# RP2040_Microcontroller.net
KiCad netlist of a schematic drawn in Altium Designer
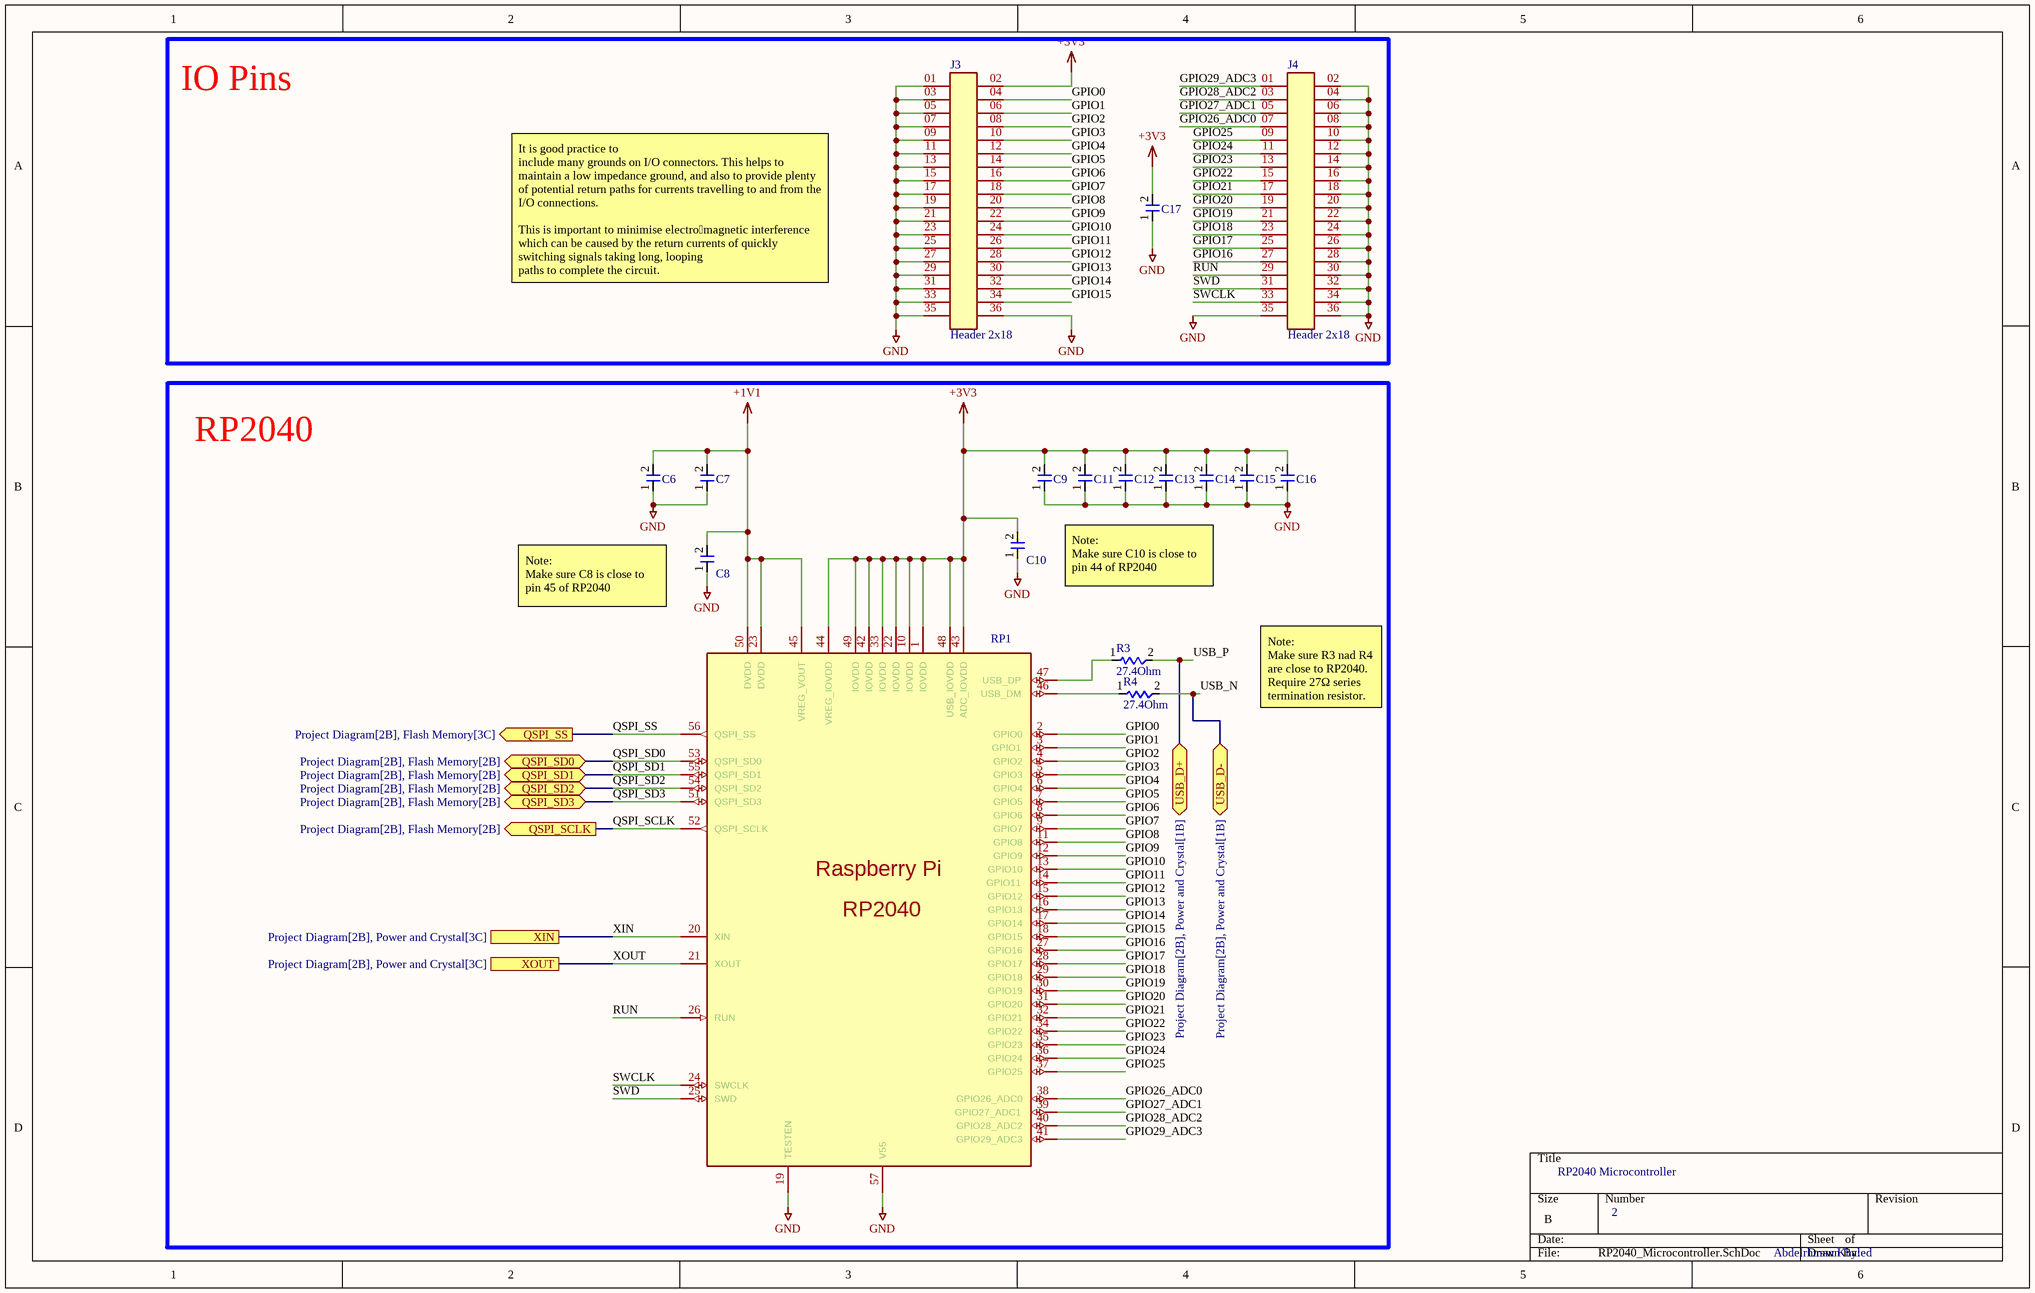
[diagram p0: RP2040_Microcontroller.SchDoc]

(export (version "E")
  (design (tool "Eeschema 10.0.6"))
  (components
    (comp (ref "C6")
      (value "100 nF")
      (footprint "CC0603KRX5R8BB104")
      (description "100 nF ±10% 25V Ceramic Capacitor X5R 0603 (1608 Metric)")
      (fields (field (name "PART NUMBER") "CL21A106KOQNNNE"))
      (libsource (lib "RP2040_Integrated_Library") (part "CC0603KRX5R8BB104"))
    )
    (comp (ref "C7")
      (value "100 nF")
      (footprint "CC0603KRX5R8BB104")
      (description "100 nF ±10% 25V Ceramic Capacitor X5R 0603 (1608 Metric)")
      (fields (field (name "PART NUMBER") "CL21A106KOQNNNE"))
      (libsource (lib "RP2040_Integrated_Library") (part "CC0603KRX5R8BB104"))
    )
    (comp (ref "C8")
      (value "1UF Cap")
      (footprint "C0805C105K4RAC7800")
      (description "1 µF ±10% 16V Ceramic Capacitor X7R 0805 (2012 Metric)")
      (fields (field (name "PART NUMBER") "C0805C105K4RAC7800"))
      (libsource (lib "RP2040_Integrated_Library") (part "C0805C105K4RAC7800"))
    )
    (comp (ref "C9")
      (value "100 nF")
      (footprint "CC0603KRX5R8BB104")
      (description "100 nF ±10% 25V Ceramic Capacitor X5R 0603 (1608 Metric)")
      (fields (field (name "PART NUMBER") "CL21A106KOQNNNE"))
      (libsource (lib "RP2040_Integrated_Library") (part "CC0603KRX5R8BB104"))
    )
    (comp (ref "C10")
      (value "1UF Cap")
      (footprint "C0805C105K4RAC7800")
      (description "1 µF ±10% 16V Ceramic Capacitor X7R 0805 (2012 Metric)")
      (fields (field (name "PART NUMBER") "C0805C105K4RAC7800"))
      (libsource (lib "RP2040_Integrated_Library") (part "C0805C105K4RAC7800"))
    )
    (comp (ref "C11")
      (value "100 nF")
      (footprint "CC0603KRX5R8BB104")
      (description "100 nF ±10% 25V Ceramic Capacitor X5R 0603 (1608 Metric)")
      (fields (field (name "PART NUMBER") "CL21A106KOQNNNE"))
      (libsource (lib "RP2040_Integrated_Library") (part "CC0603KRX5R8BB104"))
    )
    (comp (ref "C12")
      (value "100 nF")
      (footprint "CC0603KRX5R8BB104")
      (description "100 nF ±10% 25V Ceramic Capacitor X5R 0603 (1608 Metric)")
      (fields (field (name "PART NUMBER") "CL21A106KOQNNNE"))
      (libsource (lib "RP2040_Integrated_Library") (part "CC0603KRX5R8BB104"))
    )
    (comp (ref "C13")
      (value "100 nF")
      (footprint "CC0603KRX5R8BB104")
      (description "100 nF ±10% 25V Ceramic Capacitor X5R 0603 (1608 Metric)")
      (fields (field (name "PART NUMBER") "CL21A106KOQNNNE"))
      (libsource (lib "RP2040_Integrated_Library") (part "CC0603KRX5R8BB104"))
    )
    (comp (ref "C14")
      (value "100 nF")
      (footprint "CC0603KRX5R8BB104")
      (description "100 nF ±10% 25V Ceramic Capacitor X5R 0603 (1608 Metric)")
      (fields (field (name "PART NUMBER") "CL21A106KOQNNNE"))
      (libsource (lib "RP2040_Integrated_Library") (part "CC0603KRX5R8BB104"))
    )
    (comp (ref "C15")
      (value "100 nF")
      (footprint "CC0603KRX5R8BB104")
      (description "100 nF ±10% 25V Ceramic Capacitor X5R 0603 (1608 Metric)")
      (fields (field (name "PART NUMBER") "CL21A106KOQNNNE"))
      (libsource (lib "RP2040_Integrated_Library") (part "CC0603KRX5R8BB104"))
    )
    (comp (ref "C16")
      (value "100 nF")
      (footprint "CC0603KRX5R8BB104")
      (description "100 nF ±10% 25V Ceramic Capacitor X5R 0603 (1608 Metric)")
      (fields (field (name "PART NUMBER") "CL21A106KOQNNNE"))
      (libsource (lib "RP2040_Integrated_Library") (part "CC0603KRX5R8BB104"))
    )
    (comp (ref "C17")
      (value "10UF Capacitor")
      (footprint "CL21A106KOQNNNE - duplicate")
      (description "10 µF ±10% 16V Ceramic Capacitor X5R 0805 (2012 Metric)")
      (fields (field (name "PART NUMBER") "CL21A106KOQNNNE"))
      (libsource (lib "RP2040_Integrated_Library") (part "CL21A106KOQNNNE"))
    )
    (comp (ref "J3")
      (value "Header 2x18")
      (footprint "Header 2x18")
      (libsource (lib "RP2040_Integrated_Library") (part "Header 2x18"))
    )
    (comp (ref "J4")
      (value "Header 2x18")
      (footprint "Header 2x18")
      (libsource (lib "RP2040_Integrated_Library") (part "Header 2x18"))
    )
    (comp (ref "R3")
      (value "27.4Ohm")
      (footprint "RC1206FR-078K06L")
      (description "8.06 kOhms ±1% 0.25W, 1/4W Chip Resistor 1206 (3216 Metric) Moisture Resistant Thick Film")
      (fields (field (name "PART NUMBER") "RC1206FR-078K06L"))
      (libsource (lib "RP2040_Integrated_Library") (part "RC1206FR-078K06L"))
    )
    (comp (ref "R4")
      (value "27.4Ohm")
      (footprint "RC1206FR-078K06L")
      (description "8.06 kOhms ±1% 0.25W, 1/4W Chip Resistor 1206 (3216 Metric) Moisture Resistant Thick Film")
      (fields (field (name "PART NUMBER") "RC1206FR-078K06L"))
      (libsource (lib "RP2040_Integrated_Library") (part "RC1206FR-078K06L"))
    )
    (comp (ref "RP1")
      (value "CortexM0")
      (footprint "RaspberryPI2040")
      (libsource (lib "RP2040_Schematic") (part "RaspberryPI2040"))
    )
  )
  (nets
    (net (code "1") (name "+1V1") (class "Default")
      (node (ref "C6") (pin "2") (pinfunction "Pin_2_2") (pintype "passive"))
      (node (ref "C7") (pin "2") (pinfunction "Pin_2_2") (pintype "passive"))
      (node (ref "C8") (pin "2") (pinfunction "Pin_2_2") (pintype "passive"))
      (node (ref "RP1") (pin "23") (pinfunction "DVDD_23") (pintype "power_in"))
      (node (ref "RP1") (pin "45") (pinfunction "VREG_VOUT_45") (pintype "power_in"))
      (node (ref "RP1") (pin "50") (pinfunction "DVDD_50") (pintype "power_in"))
    )
    (net (code "2") (name "+3V3") (class "Default")
      (node (ref "C10") (pin "2") (pinfunction "Pin_2_2") (pintype "passive"))
      (node (ref "C11") (pin "2") (pinfunction "Pin_2_2") (pintype "passive"))
      (node (ref "C12") (pin "2") (pinfunction "Pin_2_2") (pintype "passive"))
      (node (ref "C13") (pin "2") (pinfunction "Pin_2_2") (pintype "passive"))
      (node (ref "C14") (pin "2") (pinfunction "Pin_2_2") (pintype "passive"))
      (node (ref "C15") (pin "2") (pinfunction "Pin_2_2") (pintype "passive"))
      (node (ref "C16") (pin "2") (pinfunction "Pin_2_2") (pintype "passive"))
      (node (ref "C17") (pin "2") (pinfunction "Pin_2_2") (pintype "passive"))
      (node (ref "C9") (pin "2") (pinfunction "Pin_2_2") (pintype "passive"))
      (node (ref "J3") (pin "02") (pinfunction "02_02") (pintype "passive"))
      (node (ref "RP1") (pin "1") (pinfunction "IOVDD_1") (pintype "power_in"))
      (node (ref "RP1") (pin "10") (pinfunction "IOVDD_10") (pintype "power_in"))
      (node (ref "RP1") (pin "22") (pinfunction "IOVDD_22") (pintype "power_in"))
      (node (ref "RP1") (pin "33") (pinfunction "IOVDD_33") (pintype "power_in"))
      (node (ref "RP1") (pin "42") (pinfunction "IOVDD_42") (pintype "power_in"))
      (node (ref "RP1") (pin "43") (pinfunction "ADC_IOVDD_43") (pintype "power_in"))
      (node (ref "RP1") (pin "44") (pinfunction "VREG_IOVDD_44") (pintype "power_in"))
      (node (ref "RP1") (pin "48") (pinfunction "USB_IOVDD_48") (pintype "power_in"))
      (node (ref "RP1") (pin "49") (pinfunction "IOVDD_49") (pintype "power_in"))
    )
    (net (code "3") (name "/GPIO0") (class "Default")
      (node (ref "J3") (pin "04") (pinfunction "04_04") (pintype "passive"))
      (node (ref "RP1") (pin "2") (pinfunction "GPIO0_2") (pintype "bidirectional"))
    )
    (net (code "4") (name "/GPIO1") (class "Default")
      (node (ref "J3") (pin "06") (pinfunction "06_06") (pintype "passive"))
      (node (ref "RP1") (pin "3") (pinfunction "GPIO1_3") (pintype "bidirectional"))
    )
    (net (code "5") (name "/GPIO2") (class "Default")
      (node (ref "J3") (pin "08") (pinfunction "08_08") (pintype "passive"))
      (node (ref "RP1") (pin "4") (pinfunction "GPIO2_4") (pintype "bidirectional"))
    )
    (net (code "6") (name "/GPIO3") (class "Default")
      (node (ref "J3") (pin "10") (pinfunction "10_10") (pintype "passive"))
      (node (ref "RP1") (pin "5") (pinfunction "GPIO3_5") (pintype "bidirectional"))
    )
    (net (code "7") (name "/GPIO4") (class "Default")
      (node (ref "J3") (pin "12") (pinfunction "12_12") (pintype "passive"))
      (node (ref "RP1") (pin "6") (pinfunction "GPIO4_6") (pintype "bidirectional"))
    )
    (net (code "8") (name "/GPIO5") (class "Default")
      (node (ref "J3") (pin "14") (pinfunction "14_14") (pintype "passive"))
      (node (ref "RP1") (pin "7") (pinfunction "GPIO5_7") (pintype "bidirectional"))
    )
    (net (code "9") (name "/GPIO6") (class "Default")
      (node (ref "J3") (pin "16") (pinfunction "16_16") (pintype "passive"))
      (node (ref "RP1") (pin "8") (pinfunction "GPIO6_8") (pintype "bidirectional"))
    )
    (net (code "10") (name "/GPIO7") (class "Default")
      (node (ref "J3") (pin "18") (pinfunction "18_18") (pintype "passive"))
      (node (ref "RP1") (pin "9") (pinfunction "GPIO7_9") (pintype "bidirectional"))
    )
    (net (code "11") (name "/GPIO8") (class "Default")
      (node (ref "J3") (pin "20") (pinfunction "20_20") (pintype "passive"))
      (node (ref "RP1") (pin "11") (pinfunction "GPIO8_11") (pintype "bidirectional"))
    )
    (net (code "12") (name "/GPIO9") (class "Default")
      (node (ref "J3") (pin "22") (pinfunction "22_22") (pintype "passive"))
      (node (ref "RP1") (pin "12") (pinfunction "GPIO9_12") (pintype "bidirectional"))
    )
    (net (code "13") (name "/GPIO10") (class "Default")
      (node (ref "J3") (pin "24") (pinfunction "24_24") (pintype "passive"))
      (node (ref "RP1") (pin "13") (pinfunction "GPIO10_13") (pintype "bidirectional"))
    )
    (net (code "14") (name "/GPIO11") (class "Default")
      (node (ref "J3") (pin "26") (pinfunction "26_26") (pintype "passive"))
      (node (ref "RP1") (pin "14") (pinfunction "GPIO11_14") (pintype "bidirectional"))
    )
    (net (code "15") (name "/GPIO12") (class "Default")
      (node (ref "J3") (pin "28") (pinfunction "28_28") (pintype "passive"))
      (node (ref "RP1") (pin "15") (pinfunction "GPIO12_15") (pintype "bidirectional"))
    )
    (net (code "16") (name "/GPIO13") (class "Default")
      (node (ref "J3") (pin "30") (pinfunction "30_30") (pintype "passive"))
      (node (ref "RP1") (pin "16") (pinfunction "GPIO13_16") (pintype "bidirectional"))
    )
    (net (code "17") (name "/GPIO14") (class "Default")
      (node (ref "J3") (pin "32") (pinfunction "32_32") (pintype "passive"))
      (node (ref "RP1") (pin "17") (pinfunction "GPIO14_17") (pintype "bidirectional"))
    )
    (net (code "18") (name "/GPIO15") (class "Default")
      (node (ref "J3") (pin "34") (pinfunction "34_34") (pintype "passive"))
      (node (ref "RP1") (pin "18") (pinfunction "GPIO15_18") (pintype "bidirectional"))
    )
    (net (code "19") (name "/GPIO16") (class "Default")
      (node (ref "J4") (pin "27") (pinfunction "27_27") (pintype "passive"))
      (node (ref "RP1") (pin "27") (pinfunction "GPIO16_27") (pintype "bidirectional"))
    )
    (net (code "20") (name "/GPIO17") (class "Default")
      (node (ref "J4") (pin "25") (pinfunction "25_25") (pintype "passive"))
      (node (ref "RP1") (pin "28") (pinfunction "GPIO17_28") (pintype "bidirectional"))
    )
    (net (code "21") (name "/GPIO18") (class "Default")
      (node (ref "J4") (pin "23") (pinfunction "23_23") (pintype "passive"))
      (node (ref "RP1") (pin "29") (pinfunction "GPIO18_29") (pintype "bidirectional"))
    )
    (net (code "22") (name "/GPIO19") (class "Default")
      (node (ref "J4") (pin "21") (pinfunction "21_21") (pintype "passive"))
      (node (ref "RP1") (pin "30") (pinfunction "GPIO19_30") (pintype "bidirectional"))
    )
    (net (code "23") (name "/GPIO20") (class "Default")
      (node (ref "J4") (pin "19") (pinfunction "19_19") (pintype "passive"))
      (node (ref "RP1") (pin "31") (pinfunction "GPIO20_31") (pintype "bidirectional"))
    )
    (net (code "24") (name "/GPIO21") (class "Default")
      (node (ref "J4") (pin "17") (pinfunction "17_17") (pintype "passive"))
      (node (ref "RP1") (pin "32") (pinfunction "GPIO21_32") (pintype "bidirectional"))
    )
    (net (code "25") (name "/GPIO22") (class "Default")
      (node (ref "J4") (pin "15") (pinfunction "15_15") (pintype "passive"))
      (node (ref "RP1") (pin "34") (pinfunction "GPIO22_34") (pintype "bidirectional"))
    )
    (net (code "26") (name "/GPIO23") (class "Default")
      (node (ref "J4") (pin "13") (pinfunction "13_13") (pintype "passive"))
      (node (ref "RP1") (pin "35") (pinfunction "GPIO23_35") (pintype "bidirectional"))
    )
    (net (code "27") (name "/GPIO24") (class "Default")
      (node (ref "J4") (pin "11") (pinfunction "11_11") (pintype "passive"))
      (node (ref "RP1") (pin "36") (pinfunction "GPIO24_36") (pintype "bidirectional"))
    )
    (net (code "28") (name "/GPIO25") (class "Default")
      (node (ref "J4") (pin "09") (pinfunction "09_09") (pintype "passive"))
      (node (ref "RP1") (pin "37") (pinfunction "GPIO25_37") (pintype "bidirectional"))
    )
    (net (code "29") (name "/GPIO26_ADC0") (class "Default")
      (node (ref "J4") (pin "07") (pinfunction "07_07") (pintype "passive"))
      (node (ref "RP1") (pin "38") (pinfunction "GPIO26_ADC0_38") (pintype "bidirectional"))
    )
    (net (code "30") (name "/GPIO27_ADC1") (class "Default")
      (node (ref "J4") (pin "05") (pinfunction "05_05") (pintype "passive"))
      (node (ref "RP1") (pin "39") (pinfunction "GPIO27_ADC1_39") (pintype "bidirectional"))
    )
    (net (code "31") (name "/GPIO28_ADC2") (class "Default")
      (node (ref "J4") (pin "03") (pinfunction "03_03") (pintype "passive"))
      (node (ref "RP1") (pin "40") (pinfunction "GPIO28_ADC2_40") (pintype "bidirectional"))
    )
    (net (code "32") (name "/GPIO29_ADC3") (class "Default")
      (node (ref "J4") (pin "01") (pinfunction "01_01") (pintype "passive"))
      (node (ref "RP1") (pin "41") (pinfunction "GPIO29_ADC3_41") (pintype "bidirectional"))
    )
    (net (code "33") (name "/QSPI_SCLK") (class "Default")
      (node (ref "RP1") (pin "52") (pinfunction "QSPI_SCLK_52") (pintype "output"))
    )
    (net (code "34") (name "/QSPI_SD0") (class "Default")
      (node (ref "RP1") (pin "53") (pinfunction "QSPI_SD0_53") (pintype "bidirectional"))
    )
    (net (code "35") (name "/QSPI_SD1") (class "Default")
      (node (ref "RP1") (pin "55") (pinfunction "QSPI_SD1_55") (pintype "bidirectional"))
    )
    (net (code "36") (name "/QSPI_SD2") (class "Default")
      (node (ref "RP1") (pin "54") (pinfunction "QSPI_SD2_54") (pintype "bidirectional"))
    )
    (net (code "37") (name "/QSPI_SD3") (class "Default")
      (node (ref "RP1") (pin "51") (pinfunction "QSPI_SD3_51") (pintype "bidirectional"))
    )
    (net (code "38") (name "/QSPI_SS") (class "Default")
      (node (ref "RP1") (pin "56") (pinfunction "QSPI_SS_56") (pintype "output"))
    )
    (net (code "39") (name "/RUN") (class "Default")
      (node (ref "J4") (pin "29") (pinfunction "29_29") (pintype "passive"))
      (node (ref "RP1") (pin "26") (pinfunction "RUN_26") (pintype "input"))
    )
    (net (code "40") (name "/SWCLK") (class "Default")
      (node (ref "J4") (pin "33") (pinfunction "33_33") (pintype "passive"))
      (node (ref "RP1") (pin "24") (pinfunction "SWCLK_24") (pintype "bidirectional"))
    )
    (net (code "41") (name "/SWD") (class "Default")
      (node (ref "J4") (pin "31") (pinfunction "31_31") (pintype "passive"))
      (node (ref "RP1") (pin "25") (pinfunction "SWD_25") (pintype "bidirectional"))
    )
    (net (code "42") (name "/USB_N") (class "Default")
      (node (ref "R4") (pin "2") (pinfunction "pin_2_2") (pintype "passive"))
    )
    (net (code "43") (name "/USB_P") (class "Default")
      (node (ref "R3") (pin "2") (pinfunction "pin_2_2") (pintype "passive"))
    )
    (net (code "44") (name "/XIN") (class "Default")
      (node (ref "RP1") (pin "20") (pinfunction "XIN_20") (pintype "passive"))
    )
    (net (code "45") (name "/XOUT") (class "Default")
      (node (ref "RP1") (pin "21") (pinfunction "XOUT_21") (pintype "passive"))
    )
    (net (code "46") (name "GND") (class "Default")
      (node (ref "C10") (pin "1") (pinfunction "Pin_1_1") (pintype "passive"))
      (node (ref "C11") (pin "1") (pinfunction "Pin_1_1") (pintype "passive"))
      (node (ref "C12") (pin "1") (pinfunction "Pin_1_1") (pintype "passive"))
      (node (ref "C13") (pin "1") (pinfunction "Pin_1_1") (pintype "passive"))
      (node (ref "C14") (pin "1") (pinfunction "Pin_1_1") (pintype "passive"))
      (node (ref "C15") (pin "1") (pinfunction "Pin_1_1") (pintype "passive"))
      (node (ref "C16") (pin "1") (pinfunction "Pin_1_1") (pintype "passive"))
      (node (ref "C17") (pin "1") (pinfunction "Pin_1_1") (pintype "passive"))
      (node (ref "C6") (pin "1") (pinfunction "Pin_1_1") (pintype "passive"))
      (node (ref "C7") (pin "1") (pinfunction "Pin_1_1") (pintype "passive"))
      (node (ref "C8") (pin "1") (pinfunction "Pin_1_1") (pintype "passive"))
      (node (ref "C9") (pin "1") (pinfunction "Pin_1_1") (pintype "passive"))
      (node (ref "J3") (pin "01") (pinfunction "01_01") (pintype "passive"))
      (node (ref "J3") (pin "03") (pinfunction "03_03") (pintype "passive"))
      (node (ref "J3") (pin "05") (pinfunction "05_05") (pintype "passive"))
      (node (ref "J3") (pin "07") (pinfunction "07_07") (pintype "passive"))
      (node (ref "J3") (pin "09") (pinfunction "09_09") (pintype "passive"))
      (node (ref "J3") (pin "11") (pinfunction "11_11") (pintype "passive"))
      (node (ref "J3") (pin "13") (pinfunction "13_13") (pintype "passive"))
      (node (ref "J3") (pin "15") (pinfunction "15_15") (pintype "passive"))
      (node (ref "J3") (pin "17") (pinfunction "17_17") (pintype "passive"))
      (node (ref "J3") (pin "19") (pinfunction "19_19") (pintype "passive"))
      (node (ref "J3") (pin "21") (pinfunction "21_21") (pintype "passive"))
      (node (ref "J3") (pin "23") (pinfunction "23_23") (pintype "passive"))
      (node (ref "J3") (pin "25") (pinfunction "25_25") (pintype "passive"))
      (node (ref "J3") (pin "27") (pinfunction "27_27") (pintype "passive"))
      (node (ref "J3") (pin "29") (pinfunction "29_29") (pintype "passive"))
      (node (ref "J3") (pin "31") (pinfunction "31_31") (pintype "passive"))
      (node (ref "J3") (pin "33") (pinfunction "33_33") (pintype "passive"))
      (node (ref "J3") (pin "35") (pinfunction "35_35") (pintype "passive"))
      (node (ref "J3") (pin "36") (pinfunction "36_36") (pintype "passive"))
      (node (ref "J4") (pin "02") (pinfunction "02_02") (pintype "passive"))
      (node (ref "J4") (pin "04") (pinfunction "04_04") (pintype "passive"))
      (node (ref "J4") (pin "06") (pinfunction "06_06") (pintype "passive"))
      (node (ref "J4") (pin "08") (pinfunction "08_08") (pintype "passive"))
      (node (ref "J4") (pin "10") (pinfunction "10_10") (pintype "passive"))
      (node (ref "J4") (pin "12") (pinfunction "12_12") (pintype "passive"))
      (node (ref "J4") (pin "14") (pinfunction "14_14") (pintype "passive"))
      (node (ref "J4") (pin "16") (pinfunction "16_16") (pintype "passive"))
      (node (ref "J4") (pin "18") (pinfunction "18_18") (pintype "passive"))
      (node (ref "J4") (pin "20") (pinfunction "20_20") (pintype "passive"))
      (node (ref "J4") (pin "22") (pinfunction "22_22") (pintype "passive"))
      (node (ref "J4") (pin "24") (pinfunction "24_24") (pintype "passive"))
      (node (ref "J4") (pin "26") (pinfunction "26_26") (pintype "passive"))
      (node (ref "J4") (pin "28") (pinfunction "28_28") (pintype "passive"))
      (node (ref "J4") (pin "30") (pinfunction "30_30") (pintype "passive"))
      (node (ref "J4") (pin "32") (pinfunction "32_32") (pintype "passive"))
      (node (ref "J4") (pin "34") (pinfunction "34_34") (pintype "passive"))
      (node (ref "J4") (pin "35") (pinfunction "35_35") (pintype "passive"))
      (node (ref "J4") (pin "36") (pinfunction "36_36") (pintype "passive"))
      (node (ref "RP1") (pin "19") (pinfunction "TESTEN_19") (pintype "power_in"))
      (node (ref "RP1") (pin "57") (pinfunction "V55_57") (pintype "power_in"))
    )
    (net (code "47") (name "Net-(R3-Pin_1)") (class "Default")
      (node (ref "R3") (pin "1") (pinfunction "Pin_1_1") (pintype "passive"))
      (node (ref "RP1") (pin "47") (pinfunction "USB_DP_47") (pintype "bidirectional"))
    )
    (net (code "48") (name "Net-(R4-Pin_1)") (class "Default")
      (node (ref "R4") (pin "1") (pinfunction "Pin_1_1") (pintype "passive"))
      (node (ref "RP1") (pin "46") (pinfunction "USB_DM_46") (pintype "bidirectional"))
    )
  )
)
